# ParaBeep_V0_1.net
KiCad netlist of a schematic drawn in EAGLE
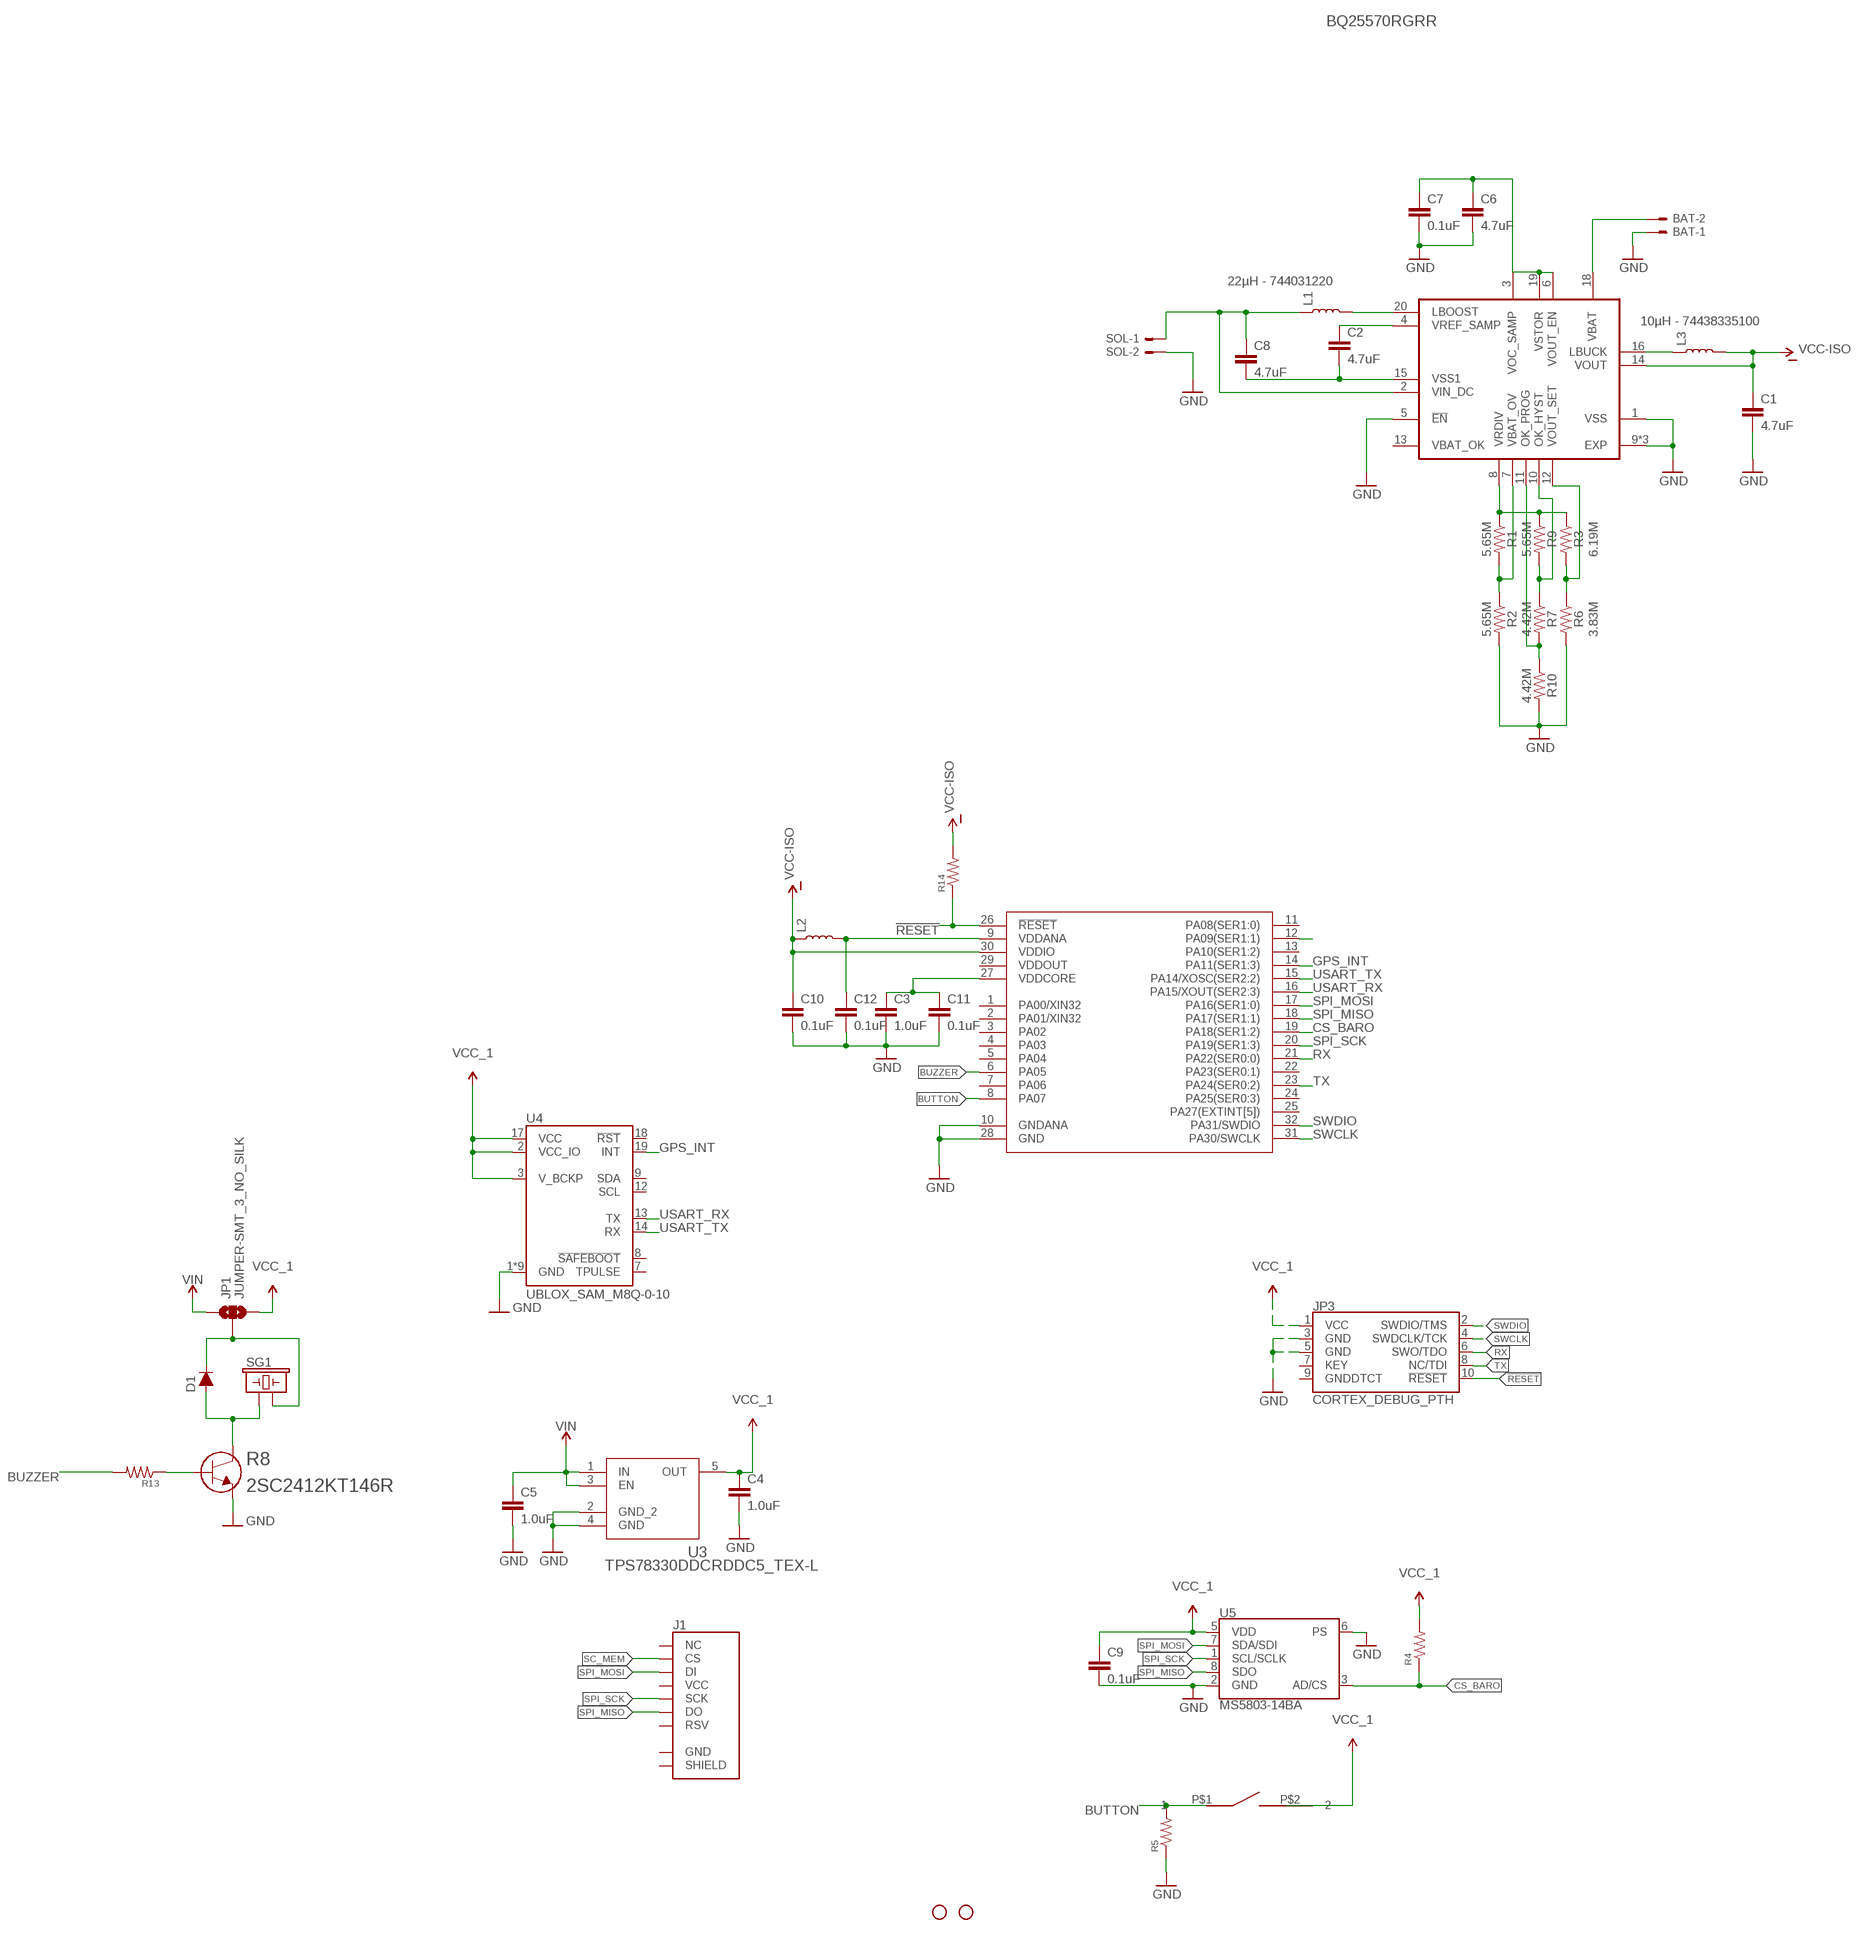
[diagram p0: schematic, sheet 1]

(export (version "E")
  (design (tool "Eeschema 10.0.6"))
  (components
    (comp (ref "BAT")
      (value "SM02B-SSR-H-TB")
      (footprint "eagle-import:SM02B-SSR-H-TB")
      (libsource (lib "eagle-import") (part "SM02B-SSR-H-TB"))
    )
    (comp (ref "C1")
      (value "4.7uF")
      (footprint "eagle-import:0603")
      (libsource (lib "eagle-import") (part "4.7UF-0603-6.3V-(10%)"))
    )
    (comp (ref "C2")
      (value "4.7uF")
      (footprint "eagle-import:0603")
      (libsource (lib "eagle-import") (part "4.7UF-0603-6.3V-(10%)"))
    )
    (comp (ref "C3")
      (value "1.0uF")
      (footprint "eagle-import:0603")
      (libsource (lib "eagle-import") (part "1.0UF-0603-16V-10%"))
    )
    (comp (ref "C4")
      (value "1.0uF")
      (footprint "eagle-import:0603")
      (libsource (lib "eagle-import") (part "1.0UF-0603-16V-10%"))
    )
    (comp (ref "C5")
      (value "1.0uF")
      (footprint "eagle-import:0603")
      (libsource (lib "eagle-import") (part "1.0UF-0603-16V-10%"))
    )
    (comp (ref "C6")
      (value "4.7uF")
      (footprint "eagle-import:0603")
      (libsource (lib "eagle-import") (part "4.7UF-0603-6.3V-(10%)"))
    )
    (comp (ref "C7")
      (value "0.1uF")
      (footprint "eagle-import:0603")
      (libsource (lib "eagle-import") (part "0.1UF-0603-25V-5%"))
    )
    (comp (ref "C8")
      (value "4.7uF")
      (footprint "eagle-import:0603")
      (libsource (lib "eagle-import") (part "4.7UF-0603-6.3V-(10%)"))
    )
    (comp (ref "C9")
      (value "0.1uF")
      (footprint "eagle-import:0603")
      (libsource (lib "eagle-import") (part "0.1UF-0603-25V-(+80/-20%)"))
    )
    (comp (ref "C10")
      (value "0.1uF")
      (footprint "eagle-import:0603")
      (libsource (lib "eagle-import") (part "0.1UF-0603-25V-(+80/-20%)"))
    )
    (comp (ref "C11")
      (value "0.1uF")
      (footprint "eagle-import:0603")
      (libsource (lib "eagle-import") (part "0.1UF-0603-25V-(+80/-20%)"))
    )
    (comp (ref "C12")
      (value "0.1uF")
      (footprint "eagle-import:0603")
      (libsource (lib "eagle-import") (part "0.1UF-0603-25V-(+80/-20%)"))
    )
    (comp (ref "D1")
      (value "250mA/100V")
      (footprint "eagle-import:SOD-323")
      (libsource (lib "eagle-import") (part "DIODE-BAS16J"))
    )
    (comp (ref "H1")
      (value "STAND-OFFTIGHT")
      (footprint "eagle-import:STAND-OFF-TIGHT")
      (libsource (lib "eagle-import") (part "STAND-OFFTIGHT"))
    )
    (comp (ref "H2")
      (value "STAND-OFFTIGHT")
      (footprint "eagle-import:STAND-OFF-TIGHT")
      (libsource (lib "eagle-import") (part "STAND-OFFTIGHT"))
    )
    (comp (ref "J1")
      (value "MICRO-SD_CARD_SOCKETPUSH-PUSH")
      (footprint "eagle-import:MICRO-SD-SOCKET")
      (libsource (lib "eagle-import") (part "MICRO-SD_CARD_SOCKETPUSH-PUSH"))
    )
    (comp (ref "JP1")
      (value "JUMPER-SMT_3_NO_SILK")
      (footprint "eagle-import:SMT-JUMPER_3_NO_SILK")
      (libsource (lib "eagle-import") (part "JUMPER-SMT_3_NO_SILK"))
    )
    (comp (ref "JP3")
      (value "CORTEX_DEBUG_PTH")
      (footprint "eagle-import:2X5-PTH-1.27MM")
      (libsource (lib "eagle-import") (part "CORTEX_DEBUG_PTH"))
    )
    (comp (ref "L1")
      (value "22µH - 744031220")
      (footprint "eagle-import:INDUCTOR_4.7UH")
      (libsource (lib "eagle-import") (part "INDUCTOR-CDRH-4.7UH"))
    )
    (comp (ref "L2")
      (value "INDUCTORFB-30OHM")
      (footprint "eagle-import:0603")
      (libsource (lib "eagle-import") (part "INDUCTORFB-30OHM"))
    )
    (comp (ref "L3")
      (value "10µH - 74438335100")
      (footprint "eagle-import:INDUCTOR_4.7UH")
      (libsource (lib "eagle-import") (part "INDUCTOR-CDRH-4.7UH"))
    )
    (comp (ref "R1")
      (value "5.65M")
      (footprint "eagle-import:0603")
      (libsource (lib "eagle-import") (part "RESISTOR0603"))
    )
    (comp (ref "R2")
      (value "5.65M")
      (footprint "eagle-import:0603")
      (libsource (lib "eagle-import") (part "RESISTOR0603"))
    )
    (comp (ref "R3")
      (value "6.19M")
      (footprint "eagle-import:0603")
      (libsource (lib "eagle-import") (part "RESISTOR0603"))
    )
    (comp (ref "R4")
      (value "RESISTOR0402")
      (footprint "eagle-import:0402")
      (libsource (lib "eagle-import") (part "RESISTOR0402"))
    )
    (comp (ref "R5")
      (value "RESISTOR0402")
      (footprint "eagle-import:0402")
      (libsource (lib "eagle-import") (part "RESISTOR0402"))
    )
    (comp (ref "R6")
      (value "3.83M")
      (footprint "eagle-import:0603")
      (libsource (lib "eagle-import") (part "RESISTOR0603"))
    )
    (comp (ref "R7")
      (value "4.42M")
      (footprint "eagle-import:0603")
      (libsource (lib "eagle-import") (part "RESISTOR0603"))
    )
    (comp (ref "R8")
      (value "2SC2412KT146R")
      (footprint "eagle-import:TRANS_2SB852K_ROM")
      (fields (field (name "COPYRIGHT") "Copyright (C) 2018 Accelerated Designs. All rights reserved"))
      (libsource (lib "eagle-import") (part "2SC2412KT146R"))
    )
    (comp (ref "R9")
      (value "5.65M")
      (footprint "eagle-import:0603")
      (libsource (lib "eagle-import") (part "RESISTOR0603"))
    )
    (comp (ref "R10")
      (value "4.42M")
      (footprint "eagle-import:0603")
      (libsource (lib "eagle-import") (part "RESISTOR0603"))
    )
    (comp (ref "R13")
      (value "RESISTOR0402")
      (footprint "eagle-import:0402")
      (libsource (lib "eagle-import") (part "RESISTOR0402"))
    )
    (comp (ref "R14")
      (value "RESISTOR0402")
      (footprint "eagle-import:0402")
      (libsource (lib "eagle-import") (part "RESISTOR0402"))
    )
    (comp (ref "SG1")
      (value "BUZZER-SMD_KIT")
      (footprint "eagle-import:BUZZER-CCV-KIT")
      (libsource (lib "eagle-import") (part "BUZZER-SMD_KIT"))
    )
    (comp (ref "SOL")
      (value "SM02B-SSR-H-TB")
      (footprint "eagle-import:SM02B-SSR-H-TB")
      (libsource (lib "eagle-import") (part "SM02B-SSR-H-TB"))
    )
    (comp (ref "U$3")
      (value "AB11AH-HC")
      (footprint "eagle-import:AB11AH-HC")
      (libsource (lib "eagle-import") (part "AB11AH-HC"))
    )
    (comp (ref "U2")
      (value "BQ25570RGRR")
      (footprint "eagle-import:QFN50P350X350X100-21N")
      (fields (field (name "DIGI-KEY_PART_NUMBER") "296-39934-1-ND") (field (name "MF") "Texas Instruments"))
      (libsource (lib "eagle-import") (part "BQ25570RGRR"))
    )
    (comp (ref "U3")
      (value "TPS78330DDCRDDC5_TEX-L")
      (footprint "eagle-import:DDC5_TEX-L")
      (fields
        (field (name "MANUFACTURER") "Texas Instruments")
        (field (name "MANUFACTURER_PART_NUMBER") "TPS78330DDCR")
      )
      (libsource (lib "eagle-import") (part "TPS78330DDCRDDC5_TEX-L"))
    )
    (comp (ref "U4")
      (value "UBLOX_SAM_M8Q-0-10")
      (footprint "eagle-import:SAM-M8Q")
      (libsource (lib "eagle-import") (part "UBLOX_SAM_M8Q-0-10"))
    )
    (comp (ref "U5")
      (value "MS5803-14BA")
      (footprint "eagle-import:MS5803")
      (libsource (lib "eagle-import") (part "MS5803-14BA"))
    )
    (comp (ref "U6")
      (value "ATSAML10E16A-AFTTQFP32_MC_MCH-L")
      (footprint "eagle-import:TQFP32_MC_MCH-L")
      (fields
        (field (name "MANUFACTURER_PART_NUMBER") "ATSAML10E16A-AFT")
        (field (name "COPYRIGHT") "Copyright (C) 2018 Accelerated Designs. All rights reserved")
      )
      (libsource (lib "eagle-import") (part "ATSAML10E16A-AFTTQFP32_MC_MCH-L"))
    )
  )
  (nets
    (net (code "1") (name "/GPS_INT") (class "Default")
      (node (ref "U4") (pin "19") (pinfunction "INT_19") (pintype "bidirectional"))
      (node (ref "U6") (pin "14") (pinfunction "PA11(SER1:3)_14") (pintype "bidirectional"))
    )
    (net (code "2") (name "/USART_RX") (class "Default")
      (node (ref "U4") (pin "13") (pinfunction "TX_13") (pintype "bidirectional"))
      (node (ref "U6") (pin "16") (pinfunction "PA15/XOUT(SER2:3)_16") (pintype "output"))
    )
    (net (code "3") (name "/USART_TX") (class "Default")
      (node (ref "U4") (pin "14") (pinfunction "RX_14") (pintype "bidirectional"))
      (node (ref "U6") (pin "15") (pinfunction "PA14/XOSC(SER2:2)_15") (pintype "bidirectional"))
    )
    (net (code "4") (name "/~{RESET}") (class "Default")
      (node (ref "JP3") (pin "10") (pinfunction "~{RESET}_10") (pintype "bidirectional"))
      (node (ref "R14") (pin "1") (pinfunction "1_1") (pintype "passive"))
      (node (ref "U6") (pin "26") (pinfunction "~{RESET}_26") (pintype "passive"))
    )
    (net (code "5") (name "BUTTON") (class "Default")
      (node (ref "R5") (pin "2") (pinfunction "2_2") (pintype "passive"))
      (node (ref "U$3") (pin "P$1") (pinfunction "1_P$1") (pintype "bidirectional"))
      (node (ref "U6") (pin "8") (pinfunction "PA07_8") (pintype "bidirectional"))
    )
    (net (code "6") (name "BUZZER") (class "Default")
      (node (ref "R13") (pin "2") (pinfunction "2_2") (pintype "passive"))
      (node (ref "U6") (pin "6") (pinfunction "PA05_6") (pintype "bidirectional"))
    )
    (net (code "7") (name "CS_BARO") (class "Default")
      (node (ref "R4") (pin "1") (pinfunction "1_1") (pintype "passive"))
      (node (ref "U5") (pin "3") (pinfunction "AD/CS_3") (pintype "bidirectional"))
      (node (ref "U6") (pin "19") (pinfunction "PA18(SER1:2)_19") (pintype "bidirectional"))
    )
    (net (code "8") (name "GND") (class "Default")
      (node (ref "BAT") (pin "1") (pinfunction "S_1") (pintype "passive"))
      (node (ref "C1") (pin "2") (pinfunction "2_2") (pintype "passive"))
      (node (ref "C10") (pin "2") (pinfunction "2_2") (pintype "passive"))
      (node (ref "C11") (pin "2") (pinfunction "2_2") (pintype "passive"))
      (node (ref "C12") (pin "2") (pinfunction "2_2") (pintype "passive"))
      (node (ref "C3") (pin "2") (pinfunction "2_2") (pintype "passive"))
      (node (ref "C4") (pin "2") (pinfunction "2_2") (pintype "passive"))
      (node (ref "C5") (pin "2") (pinfunction "2_2") (pintype "passive"))
      (node (ref "C6") (pin "2") (pinfunction "2_2") (pintype "passive"))
      (node (ref "C7") (pin "2") (pinfunction "2_2") (pintype "passive"))
      (node (ref "C9") (pin "2") (pinfunction "2_2") (pintype "passive"))
      (node (ref "JP3") (pin "3") (pinfunction "GND_3") (pintype "bidirectional"))
      (node (ref "JP3") (pin "5") (pinfunction "GND_5") (pintype "bidirectional"))
      (node (ref "R10") (pin "2") (pinfunction "2_2") (pintype "passive"))
      (node (ref "R2") (pin "2") (pinfunction "2_2") (pintype "passive"))
      (node (ref "R5") (pin "1") (pinfunction "1_1") (pintype "passive"))
      (node (ref "R6") (pin "2") (pinfunction "2_2") (pintype "passive"))
      (node (ref "R8") (pin "3") (pinfunction "EMITTER_3") (pintype "passive"))
      (node (ref "SOL") (pin "2") (pinfunction "S_2") (pintype "passive"))
      (node (ref "U2") (pin "1") (pinfunction "VSS_1") (pintype "power_in"))
      (node (ref "U2") (pin "17") (pinfunction "EXP_17") (pintype "power_in"))
      (node (ref "U2") (pin "21") (pinfunction "EXP_21") (pintype "power_in"))
      (node (ref "U2") (pin "5") (pinfunction "~{EN}_5") (pintype "input"))
      (node (ref "U2") (pin "9") (pinfunction "EXP_9") (pintype "power_in"))
      (node (ref "U3") (pin "2") (pinfunction "GND_2_2") (pintype "power_in"))
      (node (ref "U3") (pin "4") (pinfunction "GND_4") (pintype "power_in"))
      (node (ref "U4") (pin "1") (pinfunction "GND_1") (pintype "bidirectional"))
      (node (ref "U4") (pin "10") (pinfunction "GND_10") (pintype "bidirectional"))
      (node (ref "U4") (pin "11") (pinfunction "GND_11") (pintype "bidirectional"))
      (node (ref "U4") (pin "15") (pinfunction "GND_15") (pintype "bidirectional"))
      (node (ref "U4") (pin "16") (pinfunction "GND_16") (pintype "bidirectional"))
      (node (ref "U4") (pin "20") (pinfunction "GND_20") (pintype "bidirectional"))
      (node (ref "U4") (pin "4") (pinfunction "GND_4") (pintype "bidirectional"))
      (node (ref "U4") (pin "5") (pinfunction "GND_5") (pintype "bidirectional"))
      (node (ref "U4") (pin "6") (pinfunction "GND_6") (pintype "bidirectional"))
      (node (ref "U5") (pin "2") (pinfunction "GND_2") (pintype "bidirectional"))
      (node (ref "U5") (pin "6") (pinfunction "PS_6") (pintype "bidirectional"))
      (node (ref "U6") (pin "10") (pinfunction "GNDANA_10") (pintype "passive"))
      (node (ref "U6") (pin "28") (pinfunction "GND_28") (pintype "passive"))
    )
    (net (code "9") (name "Net-(BATB-S)") (class "Default")
      (node (ref "BAT") (pin "2") (pinfunction "S_2") (pintype "passive"))
      (node (ref "U2") (pin "18") (pinfunction "VBAT_18") (pintype "power_in"))
    )
    (net (code "10") (name "Net-(L1-1)") (class "Default")
      (node (ref "C8") (pin "1") (pinfunction "1_1") (pintype "passive"))
      (node (ref "L1") (pin "P$1") (pinfunction "1_P$1") (pintype "passive"))
      (node (ref "SOL") (pin "1") (pinfunction "S_1") (pintype "passive"))
      (node (ref "U2") (pin "2") (pinfunction "VIN_DC_2") (pintype "input"))
    )
    (net (code "11") (name "Net-(L1-2)") (class "Default")
      (node (ref "L1") (pin "P$2") (pinfunction "2_P$2") (pintype "passive"))
      (node (ref "U2") (pin "20") (pinfunction "LBOOST_20") (pintype "bidirectional"))
    )
    (net (code "12") (name "Net-(L3-1)") (class "Default")
      (node (ref "L3") (pin "P$1") (pinfunction "1_P$1") (pintype "passive"))
      (node (ref "U2") (pin "16") (pinfunction "LBUCK_16") (pintype "bidirectional"))
    )
    (net (code "13") (name "Net-(R8-BASE)") (class "Default")
      (node (ref "R13") (pin "1") (pinfunction "1_1") (pintype "passive"))
      (node (ref "R8") (pin "2") (pinfunction "BASE_2") (pintype "passive"))
    )
    (net (code "14") (name "Net-(R8-COLLECTOR)") (class "Default")
      (node (ref "D1") (pin "A") (pinfunction "A_A") (pintype "passive"))
      (node (ref "R8") (pin "1") (pinfunction "COLLECTOR_1") (pintype "passive"))
      (node (ref "SG1") (pin "+") (pinfunction "1_+") (pintype "passive"))
    )
    (net (code "15") (name "Net-(SG1-2)") (class "Default")
      (node (ref "D1") (pin "C") (pinfunction "C_C") (pintype "passive"))
      (node (ref "JP1") (pin "2") (pinfunction "2_2") (pintype "passive"))
      (node (ref "SG1") (pin "-") (pinfunction "2_-") (pintype "passive"))
    )
    (net (code "16") (name "Net-(U2-OK_HYST)") (class "Default")
      (node (ref "R7") (pin "1") (pinfunction "1_1") (pintype "passive"))
      (node (ref "R9") (pin "2") (pinfunction "2_2") (pintype "passive"))
      (node (ref "U2") (pin "10") (pinfunction "OK_HYST_10") (pintype "input"))
    )
    (net (code "17") (name "Net-(U2-OK_PROG)") (class "Default")
      (node (ref "R10") (pin "1") (pinfunction "1_1") (pintype "passive"))
      (node (ref "R7") (pin "2") (pinfunction "2_2") (pintype "passive"))
      (node (ref "U2") (pin "11") (pinfunction "OK_PROG_11") (pintype "input"))
    )
    (net (code "18") (name "Net-(U2-VBAT_OV)") (class "Default")
      (node (ref "R1") (pin "2") (pinfunction "2_2") (pintype "passive"))
      (node (ref "R2") (pin "1") (pinfunction "1_1") (pintype "passive"))
      (node (ref "U2") (pin "7") (pinfunction "VBAT_OV_7") (pintype "input"))
    )
    (net (code "19") (name "Net-(U2-VOC_SAMP)") (class "Default")
      (node (ref "C6") (pin "1") (pinfunction "1_1") (pintype "passive"))
      (node (ref "C7") (pin "1") (pinfunction "1_1") (pintype "passive"))
      (node (ref "U2") (pin "19") (pinfunction "VSTOR_19") (pintype "output"))
      (node (ref "U2") (pin "3") (pinfunction "VOC_SAMP_3") (pintype "input"))
      (node (ref "U2") (pin "6") (pinfunction "VOUT_EN_6") (pintype "input"))
    )
    (net (code "20") (name "Net-(U2-VOUT_SET)") (class "Default")
      (node (ref "R3") (pin "2") (pinfunction "2_2") (pintype "passive"))
      (node (ref "R6") (pin "1") (pinfunction "1_1") (pintype "passive"))
      (node (ref "U2") (pin "12") (pinfunction "VOUT_SET_12") (pintype "input"))
    )
    (net (code "21") (name "Net-(U2-VRDIV)") (class "Default")
      (node (ref "R1") (pin "1") (pinfunction "1_1") (pintype "passive"))
      (node (ref "R3") (pin "1") (pinfunction "1_1") (pintype "passive"))
      (node (ref "R9") (pin "1") (pinfunction "1_1") (pintype "passive"))
      (node (ref "U2") (pin "8") (pinfunction "VRDIV_8") (pintype "output"))
    )
    (net (code "22") (name "Net-(U2-VREF_SAMP)") (class "Default")
      (node (ref "C2") (pin "1") (pinfunction "1_1") (pintype "passive"))
      (node (ref "U2") (pin "4") (pinfunction "VREF_SAMP_4") (pintype "input"))
    )
    (net (code "23") (name "Net-(U2-VSS1)") (class "Default")
      (node (ref "C2") (pin "2") (pinfunction "2_2") (pintype "passive"))
      (node (ref "C8") (pin "2") (pinfunction "2_2") (pintype "passive"))
      (node (ref "U2") (pin "15") (pinfunction "VSS1_15") (pintype "power_in"))
    )
    (net (code "24") (name "Net-(U6-VDDANA)") (class "Default")
      (node (ref "C12") (pin "1") (pinfunction "1_1") (pintype "passive"))
      (node (ref "L2") (pin "2") (pinfunction "2_2") (pintype "passive"))
      (node (ref "U6") (pin "9") (pinfunction "VDDANA_9") (pintype "power_in"))
    )
    (net (code "25") (name "Net-(U6-VDDCORE)") (class "Default")
      (node (ref "C11") (pin "1") (pinfunction "1_1") (pintype "passive"))
      (node (ref "C3") (pin "1") (pinfunction "1_1") (pintype "passive"))
      (node (ref "U6") (pin "27") (pinfunction "VDDCORE_27") (pintype "power_in"))
    )
    (net (code "26") (name "RX") (class "Default")
      (node (ref "JP3") (pin "6") (pinfunction "SWO/TDO_6") (pintype "bidirectional"))
      (node (ref "U6") (pin "21") (pinfunction "PA22(SER0:0)_21") (pintype "bidirectional"))
    )
    (net (code "27") (name "SC_MEM") (class "Default")
      (node (ref "J1") (pin "CS") (pinfunction "CS_CS") (pintype "bidirectional"))
    )
    (net (code "28") (name "SPI_MISO") (class "Default")
      (node (ref "J1") (pin "DO") (pinfunction "DO_DO") (pintype "bidirectional"))
      (node (ref "U5") (pin "8") (pinfunction "SDO_8") (pintype "bidirectional"))
      (node (ref "U6") (pin "18") (pinfunction "PA17(SER1:1)_18") (pintype "bidirectional"))
    )
    (net (code "29") (name "SPI_MOSI") (class "Default")
      (node (ref "J1") (pin "DI") (pinfunction "DI_DI") (pintype "bidirectional"))
      (node (ref "U5") (pin "7") (pinfunction "SDA/SDI_7") (pintype "bidirectional"))
      (node (ref "U6") (pin "17") (pinfunction "PA16(SER1:0)_17") (pintype "bidirectional"))
    )
    (net (code "30") (name "SPI_SCK") (class "Default")
      (node (ref "J1") (pin "SCLK") (pinfunction "SCK_SCLK") (pintype "bidirectional"))
      (node (ref "U5") (pin "1") (pinfunction "SCL/SCLK_1") (pintype "bidirectional"))
      (node (ref "U6") (pin "20") (pinfunction "PA19(SER1:3)_20") (pintype "bidirectional"))
    )
    (net (code "31") (name "SWCLK") (class "Default")
      (node (ref "JP3") (pin "4") (pinfunction "SWDCLK/TCK_4") (pintype "bidirectional"))
      (node (ref "U6") (pin "31") (pinfunction "PA30/SWCLK_31") (pintype "bidirectional"))
    )
    (net (code "32") (name "SWDIO") (class "Default")
      (node (ref "JP3") (pin "2") (pinfunction "SWDIO/TMS_2") (pintype "bidirectional"))
      (node (ref "U6") (pin "32") (pinfunction "PA31/SWDIO_32") (pintype "bidirectional"))
    )
    (net (code "33") (name "TX") (class "Default")
      (node (ref "JP3") (pin "8") (pinfunction "NC/TDI_8") (pintype "bidirectional"))
      (node (ref "U6") (pin "23") (pinfunction "PA24(SER0:2)_23") (pintype "bidirectional"))
    )
    (net (code "34") (name "VCC-ISO") (class "Default")
      (node (ref "C1") (pin "1") (pinfunction "1_1") (pintype "passive"))
      (node (ref "C10") (pin "1") (pinfunction "1_1") (pintype "passive"))
      (node (ref "L2") (pin "1") (pinfunction "1_1") (pintype "passive"))
      (node (ref "L3") (pin "P$2") (pinfunction "2_P$2") (pintype "passive"))
      (node (ref "R14") (pin "2") (pinfunction "2_2") (pintype "passive"))
      (node (ref "U2") (pin "14") (pinfunction "VOUT_14") (pintype "output"))
      (node (ref "U6") (pin "30") (pinfunction "VDDIO_30") (pintype "power_in"))
    )
    (net (code "35") (name "VCC_1") (class "Default")
      (node (ref "C4") (pin "1") (pinfunction "1_1") (pintype "passive"))
      (node (ref "C9") (pin "1") (pinfunction "1_1") (pintype "passive"))
      (node (ref "JP1") (pin "3") (pinfunction "3_3") (pintype "passive"))
      (node (ref "JP3") (pin "1") (pinfunction "VCC_1") (pintype "bidirectional"))
      (node (ref "R4") (pin "2") (pinfunction "2_2") (pintype "passive"))
      (node (ref "U$3") (pin "P$2") (pinfunction "2_P$2") (pintype "bidirectional"))
      (node (ref "U3") (pin "5") (pinfunction "OUT_5") (pintype "output"))
      (node (ref "U4") (pin "17") (pinfunction "VCC_17") (pintype "bidirectional"))
      (node (ref "U4") (pin "2") (pinfunction "VCC_IO_2") (pintype "bidirectional"))
      (node (ref "U4") (pin "3") (pinfunction "V_BCKP_3") (pintype "bidirectional"))
      (node (ref "U5") (pin "5") (pinfunction "VDD_5") (pintype "bidirectional"))
    )
    (net (code "36") (name "VIN") (class "Default")
      (node (ref "C5") (pin "1") (pinfunction "1_1") (pintype "passive"))
      (node (ref "JP1") (pin "1") (pinfunction "1_1") (pintype "passive"))
      (node (ref "U3") (pin "1") (pinfunction "IN_1") (pintype "input"))
      (node (ref "U3") (pin "3") (pinfunction "EN_3") (pintype "passive"))
    )
    (net (code "37") (name "unconnected-(J1-NC-PadRSV2)") (class "Default")
      (node (ref "J1") (pin "RSV2") (pinfunction "NC_RSV2") (pintype "bidirectional"))
    )
    (net (code "38") (name "unconnected-(J1-PadGND)") (class "Default")
      (node (ref "J1") (pin "GND") (pinfunction "GND_GND") (pintype "bidirectional"))
    )
    (net (code "39") (name "unconnected-(J1-PadVCC)") (class "Default")
      (node (ref "J1") (pin "VCC") (pinfunction "VCC_VCC") (pintype "bidirectional"))
    )
    (net (code "40") (name "unconnected-(J1-RSV-PadRSV1)") (class "Default")
      (node (ref "J1") (pin "RSV1") (pinfunction "RSV_RSV1") (pintype "bidirectional"))
    )
    (net (code "41") (name "unconnected-(J1-SHIELD-PadCD1)") (class "Default")
      (node (ref "J1") (pin "CD1") (pinfunction "SHIELD_CD1") (pintype "bidirectional"))
    )
    (net (code "42") (name "unconnected-(JP3-GNDDTCT-Pad9)") (class "Default")
      (node (ref "JP3") (pin "9") (pinfunction "GNDDTCT_9") (pintype "bidirectional"))
    )
    (net (code "43") (name "unconnected-(JP3-KEY-Pad7)") (class "Default")
      (node (ref "JP3") (pin "7") (pinfunction "KEY_7") (pintype "bidirectional"))
    )
    (net (code "44") (name "unconnected-(U2-VBAT_OK-Pad13)") (class "Default")
      (node (ref "U2") (pin "13") (pinfunction "VBAT_OK_13") (pintype "output"))
    )
    (net (code "45") (name "unconnected-(U4-SCL-Pad12)") (class "Default")
      (node (ref "U4") (pin "12") (pinfunction "SCL_12") (pintype "bidirectional"))
    )
    (net (code "46") (name "unconnected-(U4-SDA-Pad9)") (class "Default")
      (node (ref "U4") (pin "9") (pinfunction "SDA_9") (pintype "bidirectional"))
    )
    (net (code "47") (name "unconnected-(U4-TPULSE-Pad7)") (class "Default")
      (node (ref "U4") (pin "7") (pinfunction "TPULSE_7") (pintype "bidirectional"))
    )
    (net (code "48") (name "unconnected-(U4-~{RST}-Pad18)") (class "Default")
      (node (ref "U4") (pin "18") (pinfunction "~{RST}_18") (pintype "bidirectional"))
    )
    (net (code "49") (name "unconnected-(U4-~{SAFEBOOT}-Pad8)") (class "Default")
      (node (ref "U4") (pin "8") (pinfunction "~{SAFEBOOT}_8") (pintype "bidirectional"))
    )
    (net (code "50") (name "unconnected-(U6-PA00{slash}XIN32-Pad1)") (class "Default")
      (node (ref "U6") (pin "1") (pinfunction "PA00/XIN32_1") (pintype "input"))
    )
    (net (code "51") (name "unconnected-(U6-PA01{slash}XIN32-Pad2)") (class "Default")
      (node (ref "U6") (pin "2") (pinfunction "PA01/XIN32_2") (pintype "input"))
    )
    (net (code "52") (name "unconnected-(U6-PA02-Pad3)") (class "Default")
      (node (ref "U6") (pin "3") (pinfunction "PA02_3") (pintype "bidirectional"))
    )
    (net (code "53") (name "unconnected-(U6-PA03-Pad4)") (class "Default")
      (node (ref "U6") (pin "4") (pinfunction "PA03_4") (pintype "bidirectional"))
    )
    (net (code "54") (name "unconnected-(U6-PA04-Pad5)") (class "Default")
      (node (ref "U6") (pin "5") (pinfunction "PA04_5") (pintype "bidirectional"))
    )
    (net (code "55") (name "unconnected-(U6-PA06-Pad7)") (class "Default")
      (node (ref "U6") (pin "7") (pinfunction "PA06_7") (pintype "bidirectional"))
    )
    (net (code "56") (name "unconnected-(U6-PA08(SER1:0)-Pad11)") (class "Default")
      (node (ref "U6") (pin "11") (pinfunction "PA08(SER1:0)_11") (pintype "bidirectional"))
    )
    (net (code "57") (name "unconnected-(U6-PA09(SER1:1)-Pad12)") (class "Default")
      (node (ref "U6") (pin "12") (pinfunction "PA09(SER1:1)_12") (pintype "bidirectional"))
    )
    (net (code "58") (name "unconnected-(U6-PA10(SER1:2)-Pad13)") (class "Default")
      (node (ref "U6") (pin "13") (pinfunction "PA10(SER1:2)_13") (pintype "bidirectional"))
    )
    (net (code "59") (name "unconnected-(U6-PA23(SER0:1)-Pad22)") (class "Default")
      (node (ref "U6") (pin "22") (pinfunction "PA23(SER0:1)_22") (pintype "bidirectional"))
    )
    (net (code "60") (name "unconnected-(U6-PA25(SER0:3)-Pad24)") (class "Default")
      (node (ref "U6") (pin "24") (pinfunction "PA25(SER0:3)_24") (pintype "bidirectional"))
    )
    (net (code "61") (name "unconnected-(U6-PA27(EXTINT[5])-Pad25)") (class "Default")
      (node (ref "U6") (pin "25") (pinfunction "PA27(EXTINT[5])_25") (pintype "bidirectional"))
    )
    (net (code "62") (name "unconnected-(U6-VDDOUT-Pad29)") (class "Default")
      (node (ref "U6") (pin "29") (pinfunction "VDDOUT_29") (pintype "output"))
    )
  )
)
